# Sheet1.net
KiCad netlist of a schematic drawn in Altium Designer
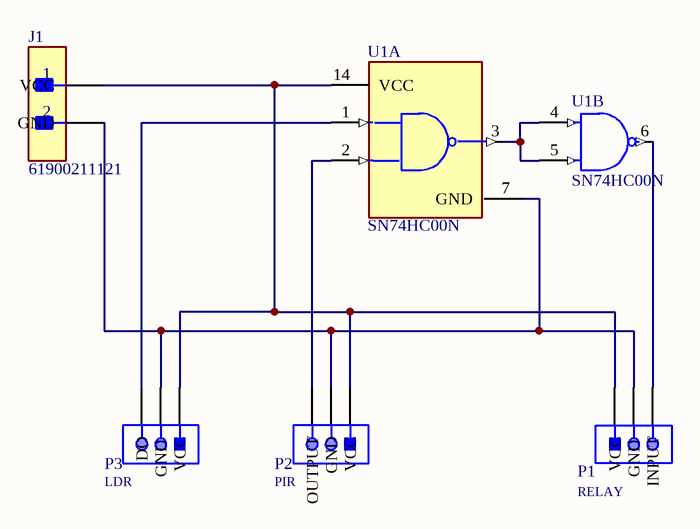
[diagram p0: Sheet1.SchDoc]

(export (version "E")
  (design (tool "Eeschema 10.0.6"))
  (components
    (comp (ref "J1")
      (value "61900211121")
      (footprint "FP-61900211121-MFG")
      (description "CONN HEADER VERT 2POS 2.54MM")
      (libsource (lib "Altium Content Vault") (part "3bc925449376181038e59eaffc5286c"))
    )
    (comp (ref "P1")
      (value "RELAY")
      (footprint "61900311121")
      (description "Male Locking Header WR-WTB, THT, Vertical, pitch 2.54 mm, 1 x 3 position")
      (fields
        (field (name "PART NUMBER") "61900311121")
        (field (name "MANUFACTURER") "Wurth Elektronik")
        (field (name "PUBLISHER") "WurthElektronik")
      )
      (libsource (lib "") (part "WE-CN-1P-M-R3_1"))
    )
    (comp (ref "P2")
      (value "PIR")
      (footprint "61900311121")
      (description "Male Locking Header WR-WTB, THT, Vertical, pitch 2.54 mm, 1 x 3 position")
      (fields
        (field (name "PART NUMBER") "61900311121")
        (field (name "MANUFACTURER") "Wurth Elektronik")
        (field (name "PUBLISHER") "WurthElektronik")
      )
      (libsource (lib "Altium Content Vault") (part "WE-CN-1P-M-R3"))
    )
    (comp (ref "P3")
      (value "LDR")
      (footprint "61900311121")
      (description "Male Locking Header WR-WTB, THT, Vertical, pitch 2.54 mm, 1 x 3 position")
      (fields
        (field (name "PART NUMBER") "61900311121")
        (field (name "MANUFACTURER") "Wurth Elektronik")
        (field (name "PUBLISHER") "WurthElektronik")
      )
      (libsource (lib "Altium Content Vault") (part "WE-CN-1P-M-R3"))
    )
    (comp (ref "U1")
      (value "SN74HC00N")
      (footprint "FP-N0014A-MFG")
      (description "IC GATE NAND 4CH 2-INP 14DIP")
      (libsource (lib "Altium Content Vault") (part "0b9c136352749c62e1c326cbc0064d4"))
    )
  )
  (nets
    (net (code "1") (name "Net-(J1-GND)") (class "Default")
      (node (ref "J1") (pin "2") (pinfunction "GND_2") (pintype "passive"))
      (node (ref "P1") (pin "2") (pinfunction "GND_2") (pintype "passive"))
      (node (ref "P2") (pin "2") (pinfunction "GND_2") (pintype "passive"))
      (node (ref "P3") (pin "2") (pinfunction "GND_2") (pintype "passive"))
      (node (ref "U1") (pin "7") (pinfunction "GND_7") (pintype "power_in"))
    )
    (net (code "2") (name "Net-(J1-VCC)") (class "Default")
      (node (ref "J1") (pin "1") (pinfunction "VCC_1") (pintype "passive"))
      (node (ref "P1") (pin "1") (pinfunction "VCC_1") (pintype "passive"))
      (node (ref "P2") (pin "1") (pinfunction "VCC_1") (pintype "passive"))
      (node (ref "P3") (pin "1") (pinfunction "VCC_1") (pintype "passive"))
      (node (ref "U1") (pin "14") (pinfunction "VCC_14") (pintype "power_in"))
    )
    (net (code "3") (name "Net-(P1-INPUT)") (class "Default")
      (node (ref "P1") (pin "3") (pinfunction "INPUT_3") (pintype "passive"))
      (node (ref "U1") (pin "6") (pinfunction "2Y_6") (pintype "output"))
    )
    (net (code "4") (name "Net-(P2-DO)") (class "Default")
      (node (ref "P2") (pin "3") (pinfunction "DO_3") (pintype "passive"))
      (node (ref "U1") (pin "2") (pinfunction "1B_2") (pintype "input"))
    )
    (net (code "5") (name "Net-(P3-DO)") (class "Default")
      (node (ref "P3") (pin "3") (pinfunction "DO_3") (pintype "passive"))
      (node (ref "U1") (pin "1") (pinfunction "1A_1") (pintype "input"))
    )
    (net (code "6") (name "Net-(U1A-1Y)") (class "Default")
      (node (ref "U1") (pin "3") (pinfunction "1Y_3") (pintype "output"))
      (node (ref "U1") (pin "4") (pinfunction "2A_4") (pintype "input"))
      (node (ref "U1") (pin "5") (pinfunction "2B_5") (pintype "input"))
    )
  )
)
